# XmegaA4U_v2_3.net
KiCad netlist of a schematic drawn in EAGLE
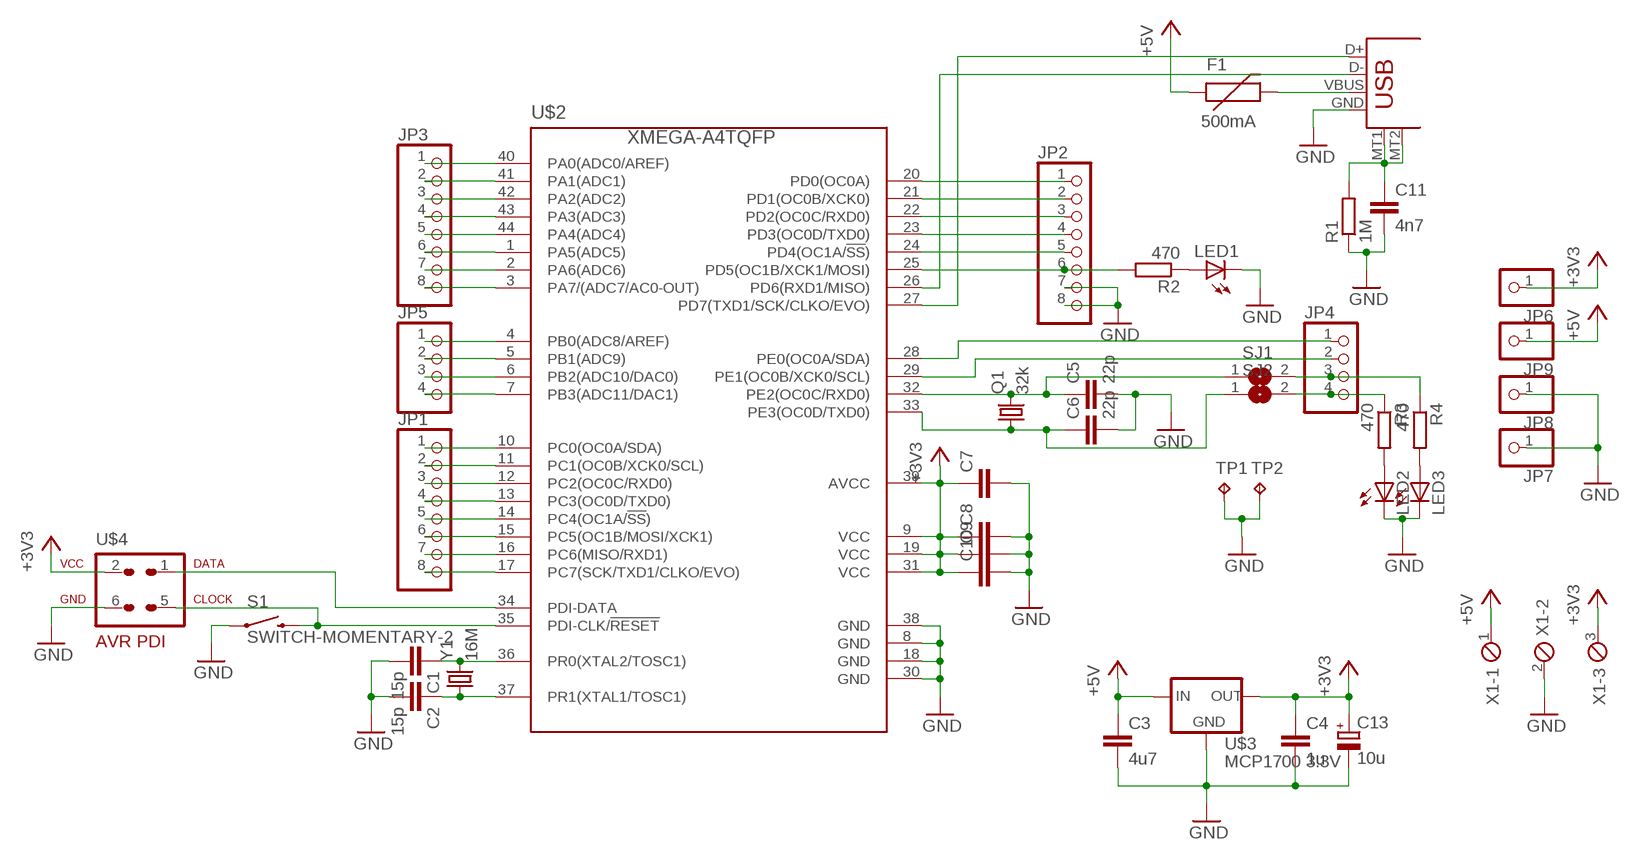
[diagram p0: schematic, sheet 1]

(export (version "E")
  (design (tool "Eeschema 10.0.6"))
  (components
    (comp (ref "C1")
      (value "15p")
      (footprint "eagle-import:C0603")
      (libsource (lib "eagle-import") (part "C-EUC0603"))
    )
    (comp (ref "C2")
      (value "15p")
      (footprint "eagle-import:C0603")
      (libsource (lib "eagle-import") (part "C-EUC0603"))
    )
    (comp (ref "C3")
      (value "4u7")
      (footprint "eagle-import:C0805")
      (libsource (lib "eagle-import") (part "C-EUC0805"))
    )
    (comp (ref "C4")
      (value "1u")
      (footprint "eagle-import:C0603")
      (libsource (lib "eagle-import") (part "C-EUC0603"))
    )
    (comp (ref "C5")
      (value "22p")
      (footprint "eagle-import:C0603")
      (libsource (lib "eagle-import") (part "C-EUC0603"))
    )
    (comp (ref "C6")
      (value "22p")
      (footprint "eagle-import:C0603")
      (libsource (lib "eagle-import") (part "C-EUC0603"))
    )
    (comp (ref "C7")
      (value "C-EUC0603")
      (footprint "eagle-import:C0603")
      (libsource (lib "eagle-import") (part "C-EUC0603"))
    )
    (comp (ref "C8")
      (value "C-EUC0603")
      (footprint "eagle-import:C0603")
      (libsource (lib "eagle-import") (part "C-EUC0603"))
    )
    (comp (ref "C9")
      (value "C-EUC0603")
      (footprint "eagle-import:C0603")
      (libsource (lib "eagle-import") (part "C-EUC0603"))
    )
    (comp (ref "C10")
      (value "C-EUC0603")
      (footprint "eagle-import:C0603")
      (libsource (lib "eagle-import") (part "C-EUC0603"))
    )
    (comp (ref "C11")
      (value "4n7")
      (footprint "eagle-import:C0603")
      (libsource (lib "eagle-import") (part "C-EUC0603"))
    )
    (comp (ref "C13")
      (value "10u")
      (footprint "eagle-import:SMC_A")
      (libsource (lib "eagle-import") (part "CPOL-EUSMCA"))
    )
    (comp (ref "F1")
      (value "500mA")
      (footprint "eagle-import:0805")
      (libsource (lib "eagle-import") (part "PTC0805"))
    )
    (comp (ref "JP1")
      (value "PINHD_FIXEDPAD_ROUND-1X8")
      (footprint "eagle-import:1X08_ROUND")
      (libsource (lib "eagle-import") (part "PINHD_FIXEDPAD_ROUND-1X8"))
    )
    (comp (ref "JP2")
      (value "PINHD_FIXEDPAD_ROUND-1X8")
      (footprint "eagle-import:1X08_ROUND")
      (libsource (lib "eagle-import") (part "PINHD_FIXEDPAD_ROUND-1X8"))
    )
    (comp (ref "JP3")
      (value "PINHD_FIXEDPAD_ROUND-1X8")
      (footprint "eagle-import:1X08_ROUND")
      (libsource (lib "eagle-import") (part "PINHD_FIXEDPAD_ROUND-1X8"))
    )
    (comp (ref "JP4")
      (value "PINHD_FIXEDPAD_ROUND-1X4")
      (footprint "eagle-import:1X04_ROUND")
      (libsource (lib "eagle-import") (part "PINHD_FIXEDPAD_ROUND-1X4"))
    )
    (comp (ref "JP5")
      (value "PINHD_FIXEDPAD_ROUND-1X4")
      (footprint "eagle-import:1X04_ROUND")
      (libsource (lib "eagle-import") (part "PINHD_FIXEDPAD_ROUND-1X4"))
    )
    (comp (ref "JP6")
      (value "PINHD_FIXEDPAD_ROUND-1X1")
      (footprint "eagle-import:1X01_ROUND")
      (libsource (lib "eagle-import") (part "PINHD_FIXEDPAD_ROUND-1X1"))
    )
    (comp (ref "JP7")
      (value "PINHD_FIXEDPAD_ROUND-1X1")
      (footprint "eagle-import:1X01_ROUND")
      (libsource (lib "eagle-import") (part "PINHD_FIXEDPAD_ROUND-1X1"))
    )
    (comp (ref "JP8")
      (value "PINHD_FIXEDPAD_ROUND-1X1")
      (footprint "eagle-import:1X01_ROUND")
      (libsource (lib "eagle-import") (part "PINHD_FIXEDPAD_ROUND-1X1"))
    )
    (comp (ref "JP9")
      (value "PINHD_FIXEDPAD_ROUND-1X1")
      (footprint "eagle-import:1X01_ROUND")
      (libsource (lib "eagle-import") (part "PINHD_FIXEDPAD_ROUND-1X1"))
    )
    (comp (ref "LED1")
      (value "LEDCHIP-LED0603")
      (footprint "eagle-import:CHIP-LED0603")
      (libsource (lib "eagle-import") (part "LEDCHIP-LED0603"))
    )
    (comp (ref "LED2")
      (value "LEDCHIP-LED0603")
      (footprint "eagle-import:CHIP-LED0603")
      (libsource (lib "eagle-import") (part "LEDCHIP-LED0603"))
    )
    (comp (ref "LED3")
      (value "LEDCHIP-LED0603")
      (footprint "eagle-import:CHIP-LED0603")
      (libsource (lib "eagle-import") (part "LEDCHIP-LED0603"))
    )
    (comp (ref "Q1")
      (value "32k")
      (footprint "eagle-import:TC26V_1.27")
      (libsource (lib "eagle-import") (part "CRYSTALTC26V_1.27"))
    )
    (comp (ref "R1")
      (value "1M")
      (footprint "eagle-import:R0603")
      (libsource (lib "eagle-import") (part "R-EU_R0603"))
    )
    (comp (ref "R2")
      (value "470")
      (footprint "eagle-import:R0603")
      (libsource (lib "eagle-import") (part "R-EU_R0603"))
    )
    (comp (ref "R3")
      (value "470")
      (footprint "eagle-import:R0603")
      (libsource (lib "eagle-import") (part "R-EU_R0603"))
    )
    (comp (ref "R4")
      (value "470")
      (footprint "eagle-import:R0603")
      (libsource (lib "eagle-import") (part "R-EU_R0603"))
    )
    (comp (ref "S1")
      (value "SWITCH-MOMENTARY-2")
      (footprint "eagle-import:TACTILE_SWITCH_TALL")
      (libsource (lib "eagle-import") (part "SWITCH-MOMENTARY-2"))
    )
    (comp (ref "SJ1")
      (value "SJ_SMALL")
      (footprint "eagle-import:SJ_2S-NO")
      (libsource (lib "eagle-import") (part "SJ_SMALL"))
    )
    (comp (ref "SJ2")
      (value "SJ_SMALL")
      (footprint "eagle-import:SJ_2S-NO")
      (libsource (lib "eagle-import") (part "SJ_SMALL"))
    )
    (comp (ref "TP1")
      (value "TPTP15R")
      (footprint "eagle-import:TP15R")
      (libsource (lib "eagle-import") (part "TPTP15R"))
    )
    (comp (ref "TP2")
      (value "TPTP15R")
      (footprint "eagle-import:TP15R")
      (libsource (lib "eagle-import") (part "TPTP15R"))
    )
    (comp (ref "U$2")
      (value "XMEGA-A4TQFP")
      (footprint "eagle-import:TQFP44")
      (libsource (lib "eagle-import") (part "XMEGA-A4TQFP"))
    )
    (comp (ref "U$3")
      (value "MCP1700 3.3V")
      (footprint "eagle-import:SOT89-W")
      (libsource (lib "eagle-import") (part "VREG_MCP1700SOT89-WIDE"))
    )
    (comp (ref "U$4")
      (value "AVR-PDIVERT")
      (footprint "eagle-import:AVR-ISP-6")
      (libsource (lib "eagle-import") (part "AVR-PDIVERT"))
    )
    (comp (ref "U$5")
      (value "USB+SHIELDMICRO")
      (footprint "eagle-import:USB-MICROB")
      (libsource (lib "eagle-import") (part "USB+SHIELDMICRO"))
    )
    (comp (ref "X1")
      (value "MPT3")
      (footprint "eagle-import:3POL254")
      (libsource (lib "eagle-import") (part "MPT3"))
    )
    (comp (ref "Y1")
      (value "16M")
      (footprint "eagle-import:CRYSTAL-SMD-5X3")
      (libsource (lib "eagle-import") (part "CRYSTAL5X3"))
    )
  )
  (nets
    (net (code "1") (name "+3V3") (class "Default")
      (node (ref "C10") (pin "1") (pinfunction "1_1") (pintype "passive"))
      (node (ref "C13") (pin "+") (pinfunction "+_+") (pintype "passive"))
      (node (ref "C4") (pin "1") (pinfunction "1_1") (pintype "passive"))
      (node (ref "C7") (pin "1") (pinfunction "1_1") (pintype "passive"))
      (node (ref "C8") (pin "1") (pinfunction "1_1") (pintype "passive"))
      (node (ref "C9") (pin "1") (pinfunction "1_1") (pintype "passive"))
      (node (ref "JP6") (pin "1") (pinfunction "1_1") (pintype "passive"))
      (node (ref "U$2") (pin "19") (pinfunction "VCC_19") (pintype "power_in"))
      (node (ref "U$2") (pin "31") (pinfunction "VCC_31") (pintype "power_in"))
      (node (ref "U$2") (pin "39") (pinfunction "AVCC_39") (pintype "power_in"))
      (node (ref "U$2") (pin "9") (pinfunction "VCC_9") (pintype "power_in"))
      (node (ref "U$3") (pin "3") (pinfunction "OUT_3") (pintype "output"))
      (node (ref "U$4") (pin "2") (pinfunction "2_2") (pintype "passive"))
      (node (ref "X1") (pin "3") (pinfunction "1_3") (pintype "passive"))
    )
    (net (code "2") (name "+5V") (class "Default")
      (node (ref "C3") (pin "1") (pinfunction "1_1") (pintype "passive"))
      (node (ref "F1") (pin "1") (pinfunction "1_1") (pintype "bidirectional"))
      (node (ref "JP9") (pin "1") (pinfunction "1_1") (pintype "passive"))
      (node (ref "U$3") (pin "2") (pinfunction "IN_2") (pintype "input"))
      (node (ref "U$3") (pin "TAB") (pinfunction "IN_TAB") (pintype "input"))
      (node (ref "X1") (pin "1") (pinfunction "1_1") (pintype "passive"))
    )
    (net (code "3") (name "GND") (class "Default")
      (node (ref "C1") (pin "2") (pinfunction "2_2") (pintype "passive"))
      (node (ref "C10") (pin "2") (pinfunction "2_2") (pintype "passive"))
      (node (ref "C11") (pin "2") (pinfunction "2_2") (pintype "passive"))
      (node (ref "C13") (pin "-") (pinfunction "-_-") (pintype "passive"))
      (node (ref "C2") (pin "2") (pinfunction "2_2") (pintype "passive"))
      (node (ref "C3") (pin "2") (pinfunction "2_2") (pintype "passive"))
      (node (ref "C4") (pin "2") (pinfunction "2_2") (pintype "passive"))
      (node (ref "C5") (pin "2") (pinfunction "2_2") (pintype "passive"))
      (node (ref "C6") (pin "2") (pinfunction "2_2") (pintype "passive"))
      (node (ref "C7") (pin "2") (pinfunction "2_2") (pintype "passive"))
      (node (ref "C8") (pin "2") (pinfunction "2_2") (pintype "passive"))
      (node (ref "C9") (pin "2") (pinfunction "2_2") (pintype "passive"))
      (node (ref "JP2") (pin "7") (pinfunction "7_7") (pintype "passive"))
      (node (ref "JP2") (pin "8") (pinfunction "8_8") (pintype "passive"))
      (node (ref "JP7") (pin "1") (pinfunction "1_1") (pintype "passive"))
      (node (ref "JP8") (pin "1") (pinfunction "1_1") (pintype "passive"))
      (node (ref "LED1") (pin "C") (pinfunction "C_C") (pintype "passive"))
      (node (ref "LED2") (pin "C") (pinfunction "C_C") (pintype "passive"))
      (node (ref "LED3") (pin "C") (pinfunction "C_C") (pintype "passive"))
      (node (ref "R1") (pin "1") (pinfunction "1_1") (pintype "passive"))
      (node (ref "S1") (pin "A2") (pinfunction "1_A2") (pintype "passive"))
      (node (ref "TP1") (pin "TP") (pinfunction "TP_TP") (pintype "input"))
      (node (ref "TP2") (pin "TP") (pinfunction "TP_TP") (pintype "input"))
      (node (ref "U$2") (pin "18") (pinfunction "GND_18") (pintype "power_in"))
      (node (ref "U$2") (pin "30") (pinfunction "GND_30") (pintype "power_in"))
      (node (ref "U$2") (pin "38") (pinfunction "GND_38") (pintype "power_in"))
      (node (ref "U$2") (pin "8") (pinfunction "GND_8") (pintype "power_in"))
      (node (ref "U$3") (pin "1") (pinfunction "GND_1") (pintype "input"))
      (node (ref "U$4") (pin "6") (pinfunction "6_6") (pintype "passive"))
      (node (ref "U$5") (pin "GND") (pinfunction "GND_GND") (pintype "bidirectional"))
      (node (ref "X1") (pin "2") (pinfunction "1_2") (pintype "passive"))
    )
    (net (code "4") (name "Net-(F1-Pad2)") (class "Default")
      (node (ref "F1") (pin "2") (pinfunction "2_2") (pintype "bidirectional"))
      (node (ref "U$5") (pin "VBUS") (pinfunction "VBUS_VBUS") (pintype "bidirectional"))
    )
    (net (code "5") (name "Net-(JP4-Pad3)") (class "Default")
      (node (ref "JP4") (pin "3") (pinfunction "3_3") (pintype "passive"))
      (node (ref "R4") (pin "1") (pinfunction "1_1") (pintype "passive"))
      (node (ref "SJ1") (pin "2") (pinfunction "2_2") (pintype "passive"))
    )
    (net (code "6") (name "Net-(JP4-Pad4)") (class "Default")
      (node (ref "JP4") (pin "4") (pinfunction "4_4") (pintype "passive"))
      (node (ref "R3") (pin "1") (pinfunction "1_1") (pintype "passive"))
      (node (ref "SJ2") (pin "2") (pinfunction "2_2") (pintype "passive"))
    )
    (net (code "7") (name "Net-(LED1-PadA)") (class "Default")
      (node (ref "LED1") (pin "A") (pinfunction "A_A") (pintype "passive"))
      (node (ref "R2") (pin "1") (pinfunction "1_1") (pintype "passive"))
    )
    (net (code "8") (name "Net-(LED2-PadA)") (class "Default")
      (node (ref "LED2") (pin "A") (pinfunction "A_A") (pintype "passive"))
      (node (ref "R3") (pin "2") (pinfunction "2_2") (pintype "passive"))
    )
    (net (code "9") (name "Net-(LED3-PadA)") (class "Default")
      (node (ref "LED3") (pin "A") (pinfunction "A_A") (pintype "passive"))
      (node (ref "R4") (pin "2") (pinfunction "2_2") (pintype "passive"))
    )
    (net (code "10") (name "Net-(S1-2)") (class "Default")
      (node (ref "S1") (pin "B2") (pinfunction "2_B2") (pintype "passive"))
      (node (ref "U$2") (pin "35") (pinfunction "PDI-CLK/~{RESET}_35") (pintype "input"))
      (node (ref "U$4") (pin "5") (pinfunction "5_5") (pintype "passive"))
    )
    (net (code "11") (name "Net-(U$2-PA0(ADC0{slash}AREF))") (class "Default")
      (node (ref "JP3") (pin "1") (pinfunction "1_1") (pintype "passive"))
      (node (ref "U$2") (pin "40") (pinfunction "PA0(ADC0/AREF)_40") (pintype "bidirectional"))
    )
    (net (code "12") (name "Net-(U$2-PA1(ADC1))") (class "Default")
      (node (ref "JP3") (pin "2") (pinfunction "2_2") (pintype "passive"))
      (node (ref "U$2") (pin "41") (pinfunction "PA1(ADC1)_41") (pintype "bidirectional"))
    )
    (net (code "13") (name "Net-(U$2-PA2(ADC2))") (class "Default")
      (node (ref "JP3") (pin "3") (pinfunction "3_3") (pintype "passive"))
      (node (ref "U$2") (pin "42") (pinfunction "PA2(ADC2)_42") (pintype "bidirectional"))
    )
    (net (code "14") (name "Net-(U$2-PA3(ADC3))") (class "Default")
      (node (ref "JP3") (pin "4") (pinfunction "4_4") (pintype "passive"))
      (node (ref "U$2") (pin "43") (pinfunction "PA3(ADC3)_43") (pintype "bidirectional"))
    )
    (net (code "15") (name "Net-(U$2-PA4(ADC4))") (class "Default")
      (node (ref "JP3") (pin "5") (pinfunction "5_5") (pintype "passive"))
      (node (ref "U$2") (pin "44") (pinfunction "PA4(ADC4)_44") (pintype "bidirectional"))
    )
    (net (code "16") (name "Net-(U$2-PA5(ADC5))") (class "Default")
      (node (ref "JP3") (pin "6") (pinfunction "6_6") (pintype "passive"))
      (node (ref "U$2") (pin "1") (pinfunction "PA5(ADC5)_1") (pintype "bidirectional"))
    )
    (net (code "17") (name "Net-(U$2-PA6(ADC6))") (class "Default")
      (node (ref "JP3") (pin "7") (pinfunction "7_7") (pintype "passive"))
      (node (ref "U$2") (pin "2") (pinfunction "PA6(ADC6)_2") (pintype "bidirectional"))
    )
    (net (code "18") (name "Net-(U$2-PA7{slash}(ADC7{slash}AC0-OUT))") (class "Default")
      (node (ref "JP3") (pin "8") (pinfunction "8_8") (pintype "passive"))
      (node (ref "U$2") (pin "3") (pinfunction "PA7/(ADC7/AC0-OUT)_3") (pintype "bidirectional"))
    )
    (net (code "19") (name "Net-(U$2-PB0(ADC8{slash}AREF))") (class "Default")
      (node (ref "JP5") (pin "1") (pinfunction "1_1") (pintype "passive"))
      (node (ref "U$2") (pin "4") (pinfunction "PB0(ADC8/AREF)_4") (pintype "bidirectional"))
    )
    (net (code "20") (name "Net-(U$2-PB1(ADC9))") (class "Default")
      (node (ref "JP5") (pin "2") (pinfunction "2_2") (pintype "passive"))
      (node (ref "U$2") (pin "5") (pinfunction "PB1(ADC9)_5") (pintype "bidirectional"))
    )
    (net (code "21") (name "Net-(U$2-PB2(ADC10{slash}DAC0))") (class "Default")
      (node (ref "JP5") (pin "3") (pinfunction "3_3") (pintype "passive"))
      (node (ref "U$2") (pin "6") (pinfunction "PB2(ADC10/DAC0)_6") (pintype "bidirectional"))
    )
    (net (code "22") (name "Net-(U$2-PB3(ADC11{slash}DAC1))") (class "Default")
      (node (ref "JP5") (pin "4") (pinfunction "4_4") (pintype "passive"))
      (node (ref "U$2") (pin "7") (pinfunction "PB3(ADC11/DAC1)_7") (pintype "bidirectional"))
    )
    (net (code "23") (name "Net-(U$2-PC0(OC0A{slash}SDA))") (class "Default")
      (node (ref "JP1") (pin "1") (pinfunction "1_1") (pintype "passive"))
      (node (ref "U$2") (pin "10") (pinfunction "PC0(OC0A/SDA)_10") (pintype "bidirectional"))
    )
    (net (code "24") (name "Net-(U$2-PC1(OC0B{slash}XCK0{slash}SCL))") (class "Default")
      (node (ref "JP1") (pin "2") (pinfunction "2_2") (pintype "passive"))
      (node (ref "U$2") (pin "11") (pinfunction "PC1(OC0B/XCK0/SCL)_11") (pintype "bidirectional"))
    )
    (net (code "25") (name "Net-(U$2-PC2(OC0C{slash}RXD0))") (class "Default")
      (node (ref "JP1") (pin "3") (pinfunction "3_3") (pintype "passive"))
      (node (ref "U$2") (pin "12") (pinfunction "PC2(OC0C/RXD0)_12") (pintype "bidirectional"))
    )
    (net (code "26") (name "Net-(U$2-PC3(OC0D{slash}TXD0))") (class "Default")
      (node (ref "JP1") (pin "4") (pinfunction "4_4") (pintype "passive"))
      (node (ref "U$2") (pin "13") (pinfunction "PC3(OC0D/TXD0)_13") (pintype "bidirectional"))
    )
    (net (code "27") (name "Net-(U$2-PC4(OC1A{slash}~{SS}))") (class "Default")
      (node (ref "JP1") (pin "5") (pinfunction "5_5") (pintype "passive"))
      (node (ref "U$2") (pin "14") (pinfunction "PC4(OC1A/~{SS})_14") (pintype "bidirectional"))
    )
    (net (code "28") (name "Net-(U$2-PC5(OC1B{slash}MOSI{slash}XCK1))") (class "Default")
      (node (ref "JP1") (pin "6") (pinfunction "6_6") (pintype "passive"))
      (node (ref "U$2") (pin "15") (pinfunction "PC5(OC1B/MOSI/XCK1)_15") (pintype "bidirectional"))
    )
    (net (code "29") (name "Net-(U$2-PC6(MISO{slash}RXD1))") (class "Default")
      (node (ref "JP1") (pin "7") (pinfunction "7_7") (pintype "passive"))
      (node (ref "U$2") (pin "16") (pinfunction "PC6(MISO/RXD1)_16") (pintype "bidirectional"))
    )
    (net (code "30") (name "Net-(U$2-PC7(SCK{slash}TXD1{slash}CLKO{slash}EVO))") (class "Default")
      (node (ref "JP1") (pin "8") (pinfunction "8_8") (pintype "passive"))
      (node (ref "U$2") (pin "17") (pinfunction "PC7(SCK/TXD1/CLKO/EVO)_17") (pintype "bidirectional"))
    )
    (net (code "31") (name "Net-(U$2-PD0(OC0A))") (class "Default")
      (node (ref "JP2") (pin "1") (pinfunction "1_1") (pintype "passive"))
      (node (ref "U$2") (pin "20") (pinfunction "PD0(OC0A)_20") (pintype "bidirectional"))
    )
    (net (code "32") (name "Net-(U$2-PD1(OC0B{slash}XCK0))") (class "Default")
      (node (ref "JP2") (pin "2") (pinfunction "2_2") (pintype "passive"))
      (node (ref "U$2") (pin "21") (pinfunction "PD1(OC0B/XCK0)_21") (pintype "bidirectional"))
    )
    (net (code "33") (name "Net-(U$2-PD2(OC0C{slash}RXD0))") (class "Default")
      (node (ref "JP2") (pin "3") (pinfunction "3_3") (pintype "passive"))
      (node (ref "U$2") (pin "22") (pinfunction "PD2(OC0C/RXD0)_22") (pintype "bidirectional"))
    )
    (net (code "34") (name "Net-(U$2-PD3(OC0D{slash}TXD0))") (class "Default")
      (node (ref "JP2") (pin "4") (pinfunction "4_4") (pintype "passive"))
      (node (ref "U$2") (pin "23") (pinfunction "PD3(OC0D/TXD0)_23") (pintype "bidirectional"))
    )
    (net (code "35") (name "Net-(U$2-PD4(OC1A{slash}~{SS}))") (class "Default")
      (node (ref "JP2") (pin "5") (pinfunction "5_5") (pintype "passive"))
      (node (ref "U$2") (pin "24") (pinfunction "PD4(OC1A/~{SS})_24") (pintype "bidirectional"))
    )
    (net (code "36") (name "Net-(U$2-PD5(OC1B{slash}XCK1{slash}MOSI))") (class "Default")
      (node (ref "JP2") (pin "6") (pinfunction "6_6") (pintype "passive"))
      (node (ref "R2") (pin "2") (pinfunction "2_2") (pintype "passive"))
      (node (ref "U$2") (pin "25") (pinfunction "PD5(OC1B/XCK1/MOSI)_25") (pintype "bidirectional"))
    )
    (net (code "37") (name "Net-(U$2-PD6(RXD1{slash}MISO))") (class "Default")
      (node (ref "U$2") (pin "26") (pinfunction "PD6(RXD1/MISO)_26") (pintype "bidirectional"))
      (node (ref "U$5") (pin "D-") (pinfunction "D-_D-") (pintype "bidirectional"))
    )
    (net (code "38") (name "Net-(U$2-PD7(TXD1{slash}SCK{slash}CLKO{slash}EVO))") (class "Default")
      (node (ref "U$2") (pin "27") (pinfunction "PD7(TXD1/SCK/CLKO/EVO)_27") (pintype "bidirectional"))
      (node (ref "U$5") (pin "D+") (pinfunction "D+_D+") (pintype "bidirectional"))
    )
    (net (code "39") (name "Net-(U$2-PDI-DATA)") (class "Default")
      (node (ref "U$2") (pin "34") (pinfunction "PDI-DATA_34") (pintype "bidirectional"))
      (node (ref "U$4") (pin "1") (pinfunction "1_1") (pintype "passive"))
    )
    (net (code "40") (name "Net-(U$2-PE0(OC0A{slash}SDA))") (class "Default")
      (node (ref "JP4") (pin "1") (pinfunction "1_1") (pintype "passive"))
      (node (ref "U$2") (pin "28") (pinfunction "PE0(OC0A/SDA)_28") (pintype "bidirectional"))
    )
    (net (code "41") (name "Net-(U$2-PE1(OC0B{slash}XCK0{slash}SCL))") (class "Default")
      (node (ref "JP4") (pin "2") (pinfunction "2_2") (pintype "passive"))
      (node (ref "U$2") (pin "29") (pinfunction "PE1(OC0B/XCK0/SCL)_29") (pintype "bidirectional"))
    )
    (net (code "42") (name "Net-(U$2-PE2(OC0C{slash}RXD0))") (class "Default")
      (node (ref "C5") (pin "1") (pinfunction "1_1") (pintype "passive"))
      (node (ref "Q1") (pin "2") (pinfunction "2_2") (pintype "passive"))
      (node (ref "SJ1") (pin "1") (pinfunction "1_1") (pintype "passive"))
      (node (ref "U$2") (pin "32") (pinfunction "PE2(OC0C/RXD0)_32") (pintype "bidirectional"))
    )
    (net (code "43") (name "Net-(U$2-PE3(OC0D{slash}TXD0))") (class "Default")
      (node (ref "C6") (pin "1") (pinfunction "1_1") (pintype "passive"))
      (node (ref "Q1") (pin "1") (pinfunction "1_1") (pintype "passive"))
      (node (ref "SJ2") (pin "1") (pinfunction "1_1") (pintype "passive"))
      (node (ref "U$2") (pin "33") (pinfunction "PE3(OC0D/TXD0)_33") (pintype "bidirectional"))
    )
    (net (code "44") (name "Net-(U$2-PR0(XTAL2{slash}TOSC1))") (class "Default")
      (node (ref "C1") (pin "1") (pinfunction "1_1") (pintype "passive"))
      (node (ref "U$2") (pin "36") (pinfunction "PR0(XTAL2/TOSC1)_36") (pintype "bidirectional"))
      (node (ref "Y1") (pin "3") (pinfunction "2_3") (pintype "passive"))
    )
    (net (code "45") (name "Net-(U$2-PR1(XTAL1{slash}TOSC1))") (class "Default")
      (node (ref "C2") (pin "1") (pinfunction "1_1") (pintype "passive"))
      (node (ref "U$2") (pin "37") (pinfunction "PR1(XTAL1/TOSC1)_37") (pintype "bidirectional"))
      (node (ref "Y1") (pin "1") (pinfunction "1_1") (pintype "passive"))
    )
    (net (code "46") (name "Net-(U$5-P$1)") (class "Default")
      (node (ref "C11") (pin "1") (pinfunction "1_1") (pintype "passive"))
      (node (ref "R1") (pin "2") (pinfunction "2_2") (pintype "passive"))
      (node (ref "U$5") (pin "MT1") (pinfunction "P$1_MT1") (pintype "bidirectional"))
      (node (ref "U$5") (pin "MT2") (pinfunction "P$2_MT2") (pintype "bidirectional"))
    )
  )
)
